# 4ch_audio_hub.net
KiCad netlist of a schematic drawn in EAGLE
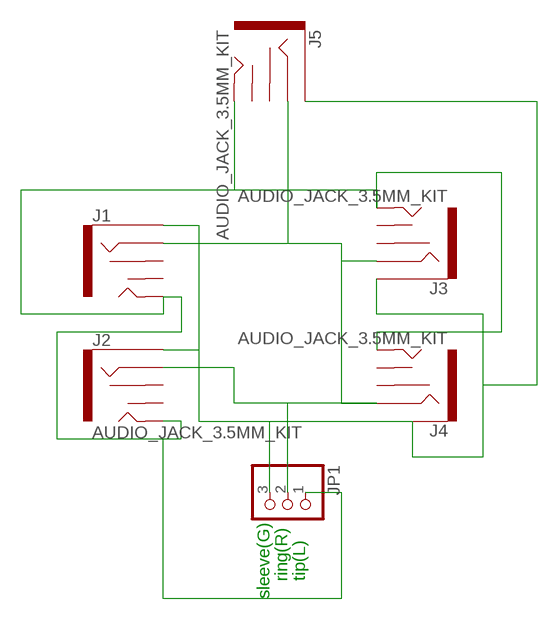
[diagram p0: schematic, sheet 1]

(export (version "E")
  (design (tool "Eeschema 10.0.6"))
  (components
    (comp (ref "J1")
      (value "ring")
      (footprint "eagle-import:AUDIO-JACK-KIT")
      (libsource (lib "eagle-import") (part "AUDIO_JACK_3.5MM_KIT"))
    )
    (comp (ref "J2")
      (value "AUDIO_JACK_3.5MM_KIT")
      (footprint "eagle-import:AUDIO-JACK-KIT")
      (libsource (lib "eagle-import") (part "AUDIO_JACK_3.5MM_KIT"))
    )
    (comp (ref "J3")
      (value "AUDIO_JACK_3.5MM_KIT")
      (footprint "eagle-import:AUDIO-JACK-KIT")
      (libsource (lib "eagle-import") (part "AUDIO_JACK_3.5MM_KIT"))
    )
    (comp (ref "J4")
      (value "AUDIO_JACK_3.5MM_KIT")
      (footprint "eagle-import:AUDIO-JACK-KIT")
      (libsource (lib "eagle-import") (part "AUDIO_JACK_3.5MM_KIT"))
    )
    (comp (ref "J5")
      (value "AUDIO_JACK_3.5MM_KIT")
      (footprint "eagle-import:AUDIO-JACK-KIT")
      (libsource (lib "eagle-import") (part "AUDIO_JACK_3.5MM_KIT"))
    )
    (comp (ref "JP1")
      (value "PINHD-1X3")
      (footprint "eagle-import:1X03")
      (libsource (lib "eagle-import") (part "PINHD-1X3"))
    )
  )
  (nets
    (net (code "1") (name "Net-(J1-PadRING)") (class "Default")
      (node (ref "J1") (pin "RING") (pinfunction "RING_RING") (pintype "bidirectional"))
      (node (ref "J2") (pin "RING") (pinfunction "RING_RING") (pintype "bidirectional"))
      (node (ref "J3") (pin "RING") (pinfunction "RING_RING") (pintype "bidirectional"))
      (node (ref "J4") (pin "RING") (pinfunction "RING_RING") (pintype "bidirectional"))
      (node (ref "J5") (pin "RING") (pinfunction "RING_RING") (pintype "bidirectional"))
      (node (ref "JP1") (pin "2") (pinfunction "2_2") (pintype "passive"))
    )
    (net (code "2") (name "Net-(J1-PadSLEEVE)") (class "Default")
      (node (ref "J1") (pin "SLEEVE") (pinfunction "SLEEVE_SLEEVE") (pintype "bidirectional"))
      (node (ref "J2") (pin "SLEEVE") (pinfunction "SLEEVE_SLEEVE") (pintype "bidirectional"))
      (node (ref "J3") (pin "SLEEVE") (pinfunction "SLEEVE_SLEEVE") (pintype "bidirectional"))
      (node (ref "J4") (pin "SLEEVE") (pinfunction "SLEEVE_SLEEVE") (pintype "bidirectional"))
      (node (ref "J5") (pin "SLEEVE") (pinfunction "SLEEVE_SLEEVE") (pintype "bidirectional"))
      (node (ref "JP1") (pin "3") (pinfunction "3_3") (pintype "passive"))
    )
    (net (code "3") (name "Net-(J1-PadTIP)") (class "Default")
      (node (ref "J1") (pin "TIP") (pinfunction "TIP_TIP") (pintype "bidirectional"))
      (node (ref "J2") (pin "TIP") (pinfunction "TIP_TIP") (pintype "bidirectional"))
      (node (ref "J3") (pin "TIP") (pinfunction "TIP_TIP") (pintype "bidirectional"))
      (node (ref "J4") (pin "TIP") (pinfunction "TIP_TIP") (pintype "bidirectional"))
      (node (ref "J5") (pin "TIP") (pinfunction "TIP_TIP") (pintype "bidirectional"))
      (node (ref "JP1") (pin "1") (pinfunction "1_1") (pintype "passive"))
    )
    (net (code "4") (name "unconnected-(J1-PadRSH)") (class "Default")
      (node (ref "J1") (pin "RSH") (pinfunction "RSH_RSH") (pintype "bidirectional"))
    )
    (net (code "5") (name "unconnected-(J1-PadTSH)") (class "Default")
      (node (ref "J1") (pin "TSH") (pinfunction "TSH_TSH") (pintype "bidirectional"))
    )
    (net (code "6") (name "unconnected-(J2-PadRSH)") (class "Default")
      (node (ref "J2") (pin "RSH") (pinfunction "RSH_RSH") (pintype "bidirectional"))
    )
    (net (code "7") (name "unconnected-(J2-PadTSH)") (class "Default")
      (node (ref "J2") (pin "TSH") (pinfunction "TSH_TSH") (pintype "bidirectional"))
    )
    (net (code "8") (name "unconnected-(J3-PadRSH)") (class "Default")
      (node (ref "J3") (pin "RSH") (pinfunction "RSH_RSH") (pintype "bidirectional"))
    )
    (net (code "9") (name "unconnected-(J3-PadTSH)") (class "Default")
      (node (ref "J3") (pin "TSH") (pinfunction "TSH_TSH") (pintype "bidirectional"))
    )
    (net (code "10") (name "unconnected-(J4-PadRSH)") (class "Default")
      (node (ref "J4") (pin "RSH") (pinfunction "RSH_RSH") (pintype "bidirectional"))
    )
    (net (code "11") (name "unconnected-(J4-PadTSH)") (class "Default")
      (node (ref "J4") (pin "TSH") (pinfunction "TSH_TSH") (pintype "bidirectional"))
    )
    (net (code "12") (name "unconnected-(J5-PadRSH)") (class "Default")
      (node (ref "J5") (pin "RSH") (pinfunction "RSH_RSH") (pintype "bidirectional"))
    )
    (net (code "13") (name "unconnected-(J5-PadTSH)") (class "Default")
      (node (ref "J5") (pin "TSH") (pinfunction "TSH_TSH") (pintype "bidirectional"))
    )
  )
)
